# cloud_humidity_sensor_v1.net
KiCad netlist of a schematic drawn in EAGLE
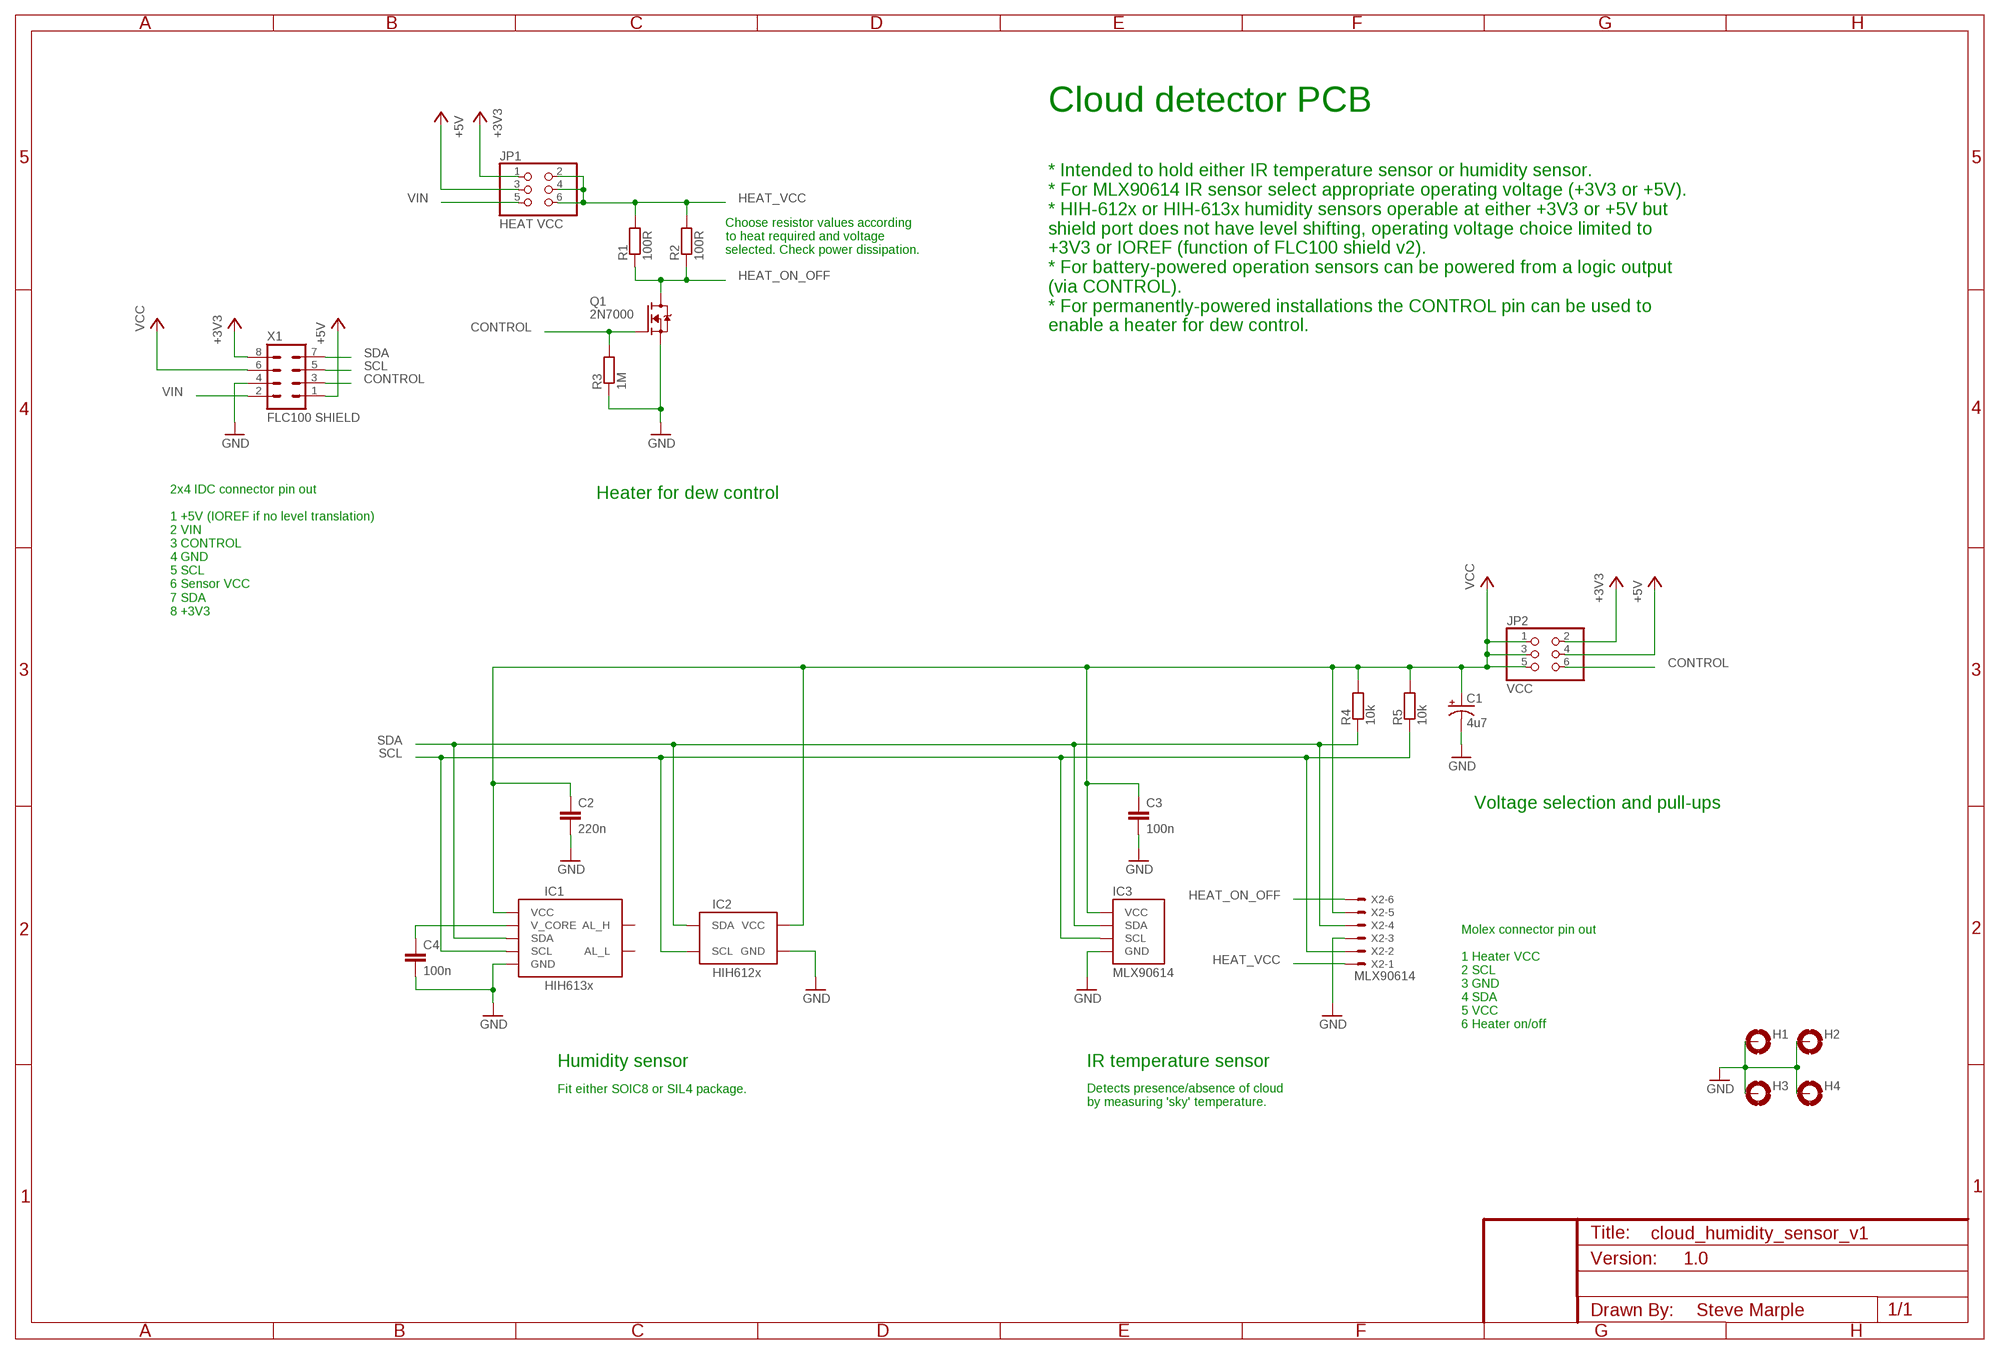
[diagram p0: schematic, sheet 1]

(export (version "E")
  (design (tool "Eeschema 10.0.6"))
  (components
    (comp (ref "C1")
      (value "4u7")
      (footprint "eagle-import:CPOL-RADIAL-10UF-25V")
      (libsource (lib "eagle-import") (part "CAP_POLPTH2"))
    )
    (comp (ref "C2")
      (value "220n")
      (footprint "eagle-import:CAP-PTH-SMALL")
      (libsource (lib "eagle-import") (part "CAPPTH"))
    )
    (comp (ref "C3")
      (value "100n")
      (footprint "eagle-import:CAP-PTH-SMALL")
      (libsource (lib "eagle-import") (part "CAPPTH"))
    )
    (comp (ref "C4")
      (value "100n")
      (footprint "eagle-import:CAP-PTH-SMALL")
      (libsource (lib "eagle-import") (part "CAPPTH"))
    )
    (comp (ref "H1")
      (value "MOUNT-PAD-ROUND3.0")
      (footprint "eagle-import:3,0-PAD")
      (libsource (lib "eagle-import") (part "MOUNT-PAD-ROUND3.0"))
    )
    (comp (ref "H2")
      (value "MOUNT-PAD-ROUND3.0")
      (footprint "eagle-import:3,0-PAD")
      (libsource (lib "eagle-import") (part "MOUNT-PAD-ROUND3.0"))
    )
    (comp (ref "H3")
      (value "MOUNT-PAD-ROUND3.0")
      (footprint "eagle-import:3,0-PAD")
      (libsource (lib "eagle-import") (part "MOUNT-PAD-ROUND3.0"))
    )
    (comp (ref "H4")
      (value "MOUNT-PAD-ROUND3.0")
      (footprint "eagle-import:3,0-PAD")
      (libsource (lib "eagle-import") (part "MOUNT-PAD-ROUND3.0"))
    )
    (comp (ref "IC1")
      (value "HIH613x")
      (footprint "eagle-import:SO08")
      (libsource (lib "eagle-import") (part "HONEYWELL-HIH613XSOIC8"))
    )
    (comp (ref "IC2")
      (value "HIH612x")
      (footprint "eagle-import:SIL04")
      (libsource (lib "eagle-import") (part "HONEYWELL-HIH612X"))
    )
    (comp (ref "IC3")
      (value "MLX90614")
      (footprint "eagle-import:TO39-4")
      (libsource (lib "eagle-import") (part "MLX90614TO-39"))
    )
    (comp (ref "JP1")
      (value "HEAT VCC")
      (footprint "eagle-import:2X03")
      (libsource (lib "eagle-import") (part "PINHD-2X3"))
    )
    (comp (ref "JP2")
      (value "VCC")
      (footprint "eagle-import:2X03")
      (libsource (lib "eagle-import") (part "PINHD-2X3"))
    )
    (comp (ref "Q1")
      (value "2N7000")
      (footprint "eagle-import:TO-92")
      (libsource (lib "eagle-import") (part "2N7000"))
    )
    (comp (ref "R1")
      (value "100R")
      (footprint "eagle-import:RES-AXIAL-0.4")
      (libsource (lib "eagle-import") (part "RESISTOR"))
    )
    (comp (ref "R2")
      (value "100R")
      (footprint "eagle-import:RES-AXIAL-0.4")
      (libsource (lib "eagle-import") (part "RESISTOR"))
    )
    (comp (ref "R3")
      (value "1M")
      (footprint "eagle-import:RES-AXIAL-0.4")
      (libsource (lib "eagle-import") (part "RESISTOR"))
    )
    (comp (ref "R4")
      (value "10k")
      (footprint "eagle-import:RES-AXIAL-0.4")
      (libsource (lib "eagle-import") (part "RESISTOR"))
    )
    (comp (ref "R5")
      (value "10k")
      (footprint "eagle-import:RES-AXIAL-0.4")
      (libsource (lib "eagle-import") (part "RESISTOR"))
    )
    (comp (ref "X1")
      (value "FLC100 SHIELD")
      (footprint "eagle-import:ML8")
      (libsource (lib "eagle-import") (part "ML8"))
    )
    (comp (ref "X2")
      (value "MLX90614")
      (footprint "eagle-import:22-23-2061")
      (fields (field (name "MF") "MOLEX") (field (name "MPN") "22-23-2061"))
      (libsource (lib "eagle-import") (part "22-23-2061"))
    )
  )
  (nets
    (net (code "1") (name "+3V3") (class "Default")
      (node (ref "JP1") (pin "1") (pinfunction "1_1") (pintype "passive"))
      (node (ref "JP2") (pin "2") (pinfunction "2_2") (pintype "passive"))
      (node (ref "X1") (pin "8") (pinfunction "8_8") (pintype "passive"))
    )
    (net (code "2") (name "+5V") (class "Default")
      (node (ref "JP1") (pin "3") (pinfunction "3_3") (pintype "passive"))
      (node (ref "JP2") (pin "4") (pinfunction "4_4") (pintype "passive"))
      (node (ref "X1") (pin "1") (pinfunction "1_1") (pintype "passive"))
    )
    (net (code "3") (name "/CONTROL") (class "Default")
      (node (ref "JP2") (pin "6") (pinfunction "6_6") (pintype "passive"))
      (node (ref "Q1") (pin "2") (pinfunction "G_2") (pintype "passive"))
      (node (ref "R3") (pin "P$2") (pinfunction "2_P$2") (pintype "passive"))
      (node (ref "X1") (pin "3") (pinfunction "3_3") (pintype "passive"))
    )
    (net (code "4") (name "/HEAT_ON_OFF") (class "Default")
      (node (ref "Q1") (pin "3") (pinfunction "D_3") (pintype "passive"))
      (node (ref "R1") (pin "P$1") (pinfunction "1_P$1") (pintype "passive"))
      (node (ref "R2") (pin "P$1") (pinfunction "1_P$1") (pintype "passive"))
      (node (ref "X2") (pin "6") (pinfunction "S_6") (pintype "passive"))
    )
    (net (code "5") (name "/HEAT_VCC") (class "Default")
      (node (ref "JP1") (pin "2") (pinfunction "2_2") (pintype "passive"))
      (node (ref "JP1") (pin "4") (pinfunction "4_4") (pintype "passive"))
      (node (ref "JP1") (pin "6") (pinfunction "6_6") (pintype "passive"))
      (node (ref "R1") (pin "P$2") (pinfunction "2_P$2") (pintype "passive"))
      (node (ref "R2") (pin "P$2") (pinfunction "2_P$2") (pintype "passive"))
      (node (ref "X2") (pin "1") (pinfunction "S_1") (pintype "passive"))
    )
    (net (code "6") (name "/SCL") (class "Default")
      (node (ref "IC1") (pin "3") (pinfunction "SCL_3") (pintype "bidirectional"))
      (node (ref "IC2") (pin "3") (pinfunction "SCL_3") (pintype "bidirectional"))
      (node (ref "IC3") (pin "1") (pinfunction "SCL_1") (pintype "bidirectional"))
      (node (ref "R5") (pin "P$1") (pinfunction "1_P$1") (pintype "passive"))
      (node (ref "X1") (pin "5") (pinfunction "5_5") (pintype "passive"))
      (node (ref "X2") (pin "2") (pinfunction "S_2") (pintype "passive"))
    )
    (net (code "7") (name "/SDA") (class "Default")
      (node (ref "IC1") (pin "4") (pinfunction "SDA_4") (pintype "bidirectional"))
      (node (ref "IC2") (pin "4") (pinfunction "SDA_4") (pintype "bidirectional"))
      (node (ref "IC3") (pin "2") (pinfunction "SDA_2") (pintype "bidirectional"))
      (node (ref "R4") (pin "P$1") (pinfunction "1_P$1") (pintype "passive"))
      (node (ref "X1") (pin "7") (pinfunction "7_7") (pintype "passive"))
      (node (ref "X2") (pin "4") (pinfunction "S_4") (pintype "passive"))
    )
    (net (code "8") (name "/VIN") (class "Default")
      (node (ref "JP1") (pin "5") (pinfunction "5_5") (pintype "passive"))
      (node (ref "X1") (pin "2") (pinfunction "2_2") (pintype "passive"))
    )
    (net (code "9") (name "GND") (class "Default")
      (node (ref "C1") (pin "2") (pinfunction "-_2") (pintype "passive"))
      (node (ref "C2") (pin "2") (pinfunction "2_2") (pintype "passive"))
      (node (ref "C3") (pin "2") (pinfunction "2_2") (pintype "passive"))
      (node (ref "C4") (pin "2") (pinfunction "2_2") (pintype "passive"))
      (node (ref "H1") (pin "B3,0") (pinfunction "MOUNT_B3,0") (pintype "passive"))
      (node (ref "H2") (pin "B3,0") (pinfunction "MOUNT_B3,0") (pintype "passive"))
      (node (ref "H3") (pin "B3,0") (pinfunction "MOUNT_B3,0") (pintype "passive"))
      (node (ref "H4") (pin "B3,0") (pinfunction "MOUNT_B3,0") (pintype "passive"))
      (node (ref "IC1") (pin "2") (pinfunction "GND_2") (pintype "power_in"))
      (node (ref "IC2") (pin "2") (pinfunction "GND_2") (pintype "power_in"))
      (node (ref "IC3") (pin "4") (pinfunction "GND_4") (pintype "power_in"))
      (node (ref "Q1") (pin "1") (pinfunction "S_1") (pintype "passive"))
      (node (ref "R3") (pin "P$1") (pinfunction "1_P$1") (pintype "passive"))
      (node (ref "X1") (pin "4") (pinfunction "4_4") (pintype "passive"))
      (node (ref "X2") (pin "3") (pinfunction "S_3") (pintype "passive"))
    )
    (net (code "10") (name "Net-(IC1-V_CORE)") (class "Default")
      (node (ref "C4") (pin "1") (pinfunction "1_1") (pintype "passive"))
      (node (ref "IC1") (pin "1") (pinfunction "V_CORE_1") (pintype "output"))
    )
    (net (code "11") (name "VCC") (class "Default")
      (node (ref "C1") (pin "1") (pinfunction "+_1") (pintype "passive"))
      (node (ref "C2") (pin "1") (pinfunction "1_1") (pintype "passive"))
      (node (ref "C3") (pin "1") (pinfunction "1_1") (pintype "passive"))
      (node (ref "IC1") (pin "8") (pinfunction "VCC_8") (pintype "power_in"))
      (node (ref "IC2") (pin "1") (pinfunction "VCC_1") (pintype "power_in"))
      (node (ref "IC3") (pin "3") (pinfunction "VCC_3") (pintype "power_in"))
      (node (ref "JP2") (pin "1") (pinfunction "1_1") (pintype "passive"))
      (node (ref "JP2") (pin "3") (pinfunction "3_3") (pintype "passive"))
      (node (ref "JP2") (pin "5") (pinfunction "5_5") (pintype "passive"))
      (node (ref "R4") (pin "P$2") (pinfunction "2_P$2") (pintype "passive"))
      (node (ref "R5") (pin "P$2") (pinfunction "2_P$2") (pintype "passive"))
      (node (ref "X1") (pin "6") (pinfunction "6_6") (pintype "passive"))
      (node (ref "X2") (pin "5") (pinfunction "S_5") (pintype "passive"))
    )
    (net (code "12") (name "unconnected-(IC1-AL_H-Pad5)") (class "Default")
      (node (ref "IC1") (pin "5") (pinfunction "AL_H_5") (pintype "bidirectional"))
    )
    (net (code "13") (name "unconnected-(IC1-AL_L-Pad6)") (class "Default")
      (node (ref "IC1") (pin "6") (pinfunction "AL_L_6") (pintype "bidirectional"))
    )
  )
)
